# RoboSlider.net
KiCad netlist of a schematic drawn in EAGLE
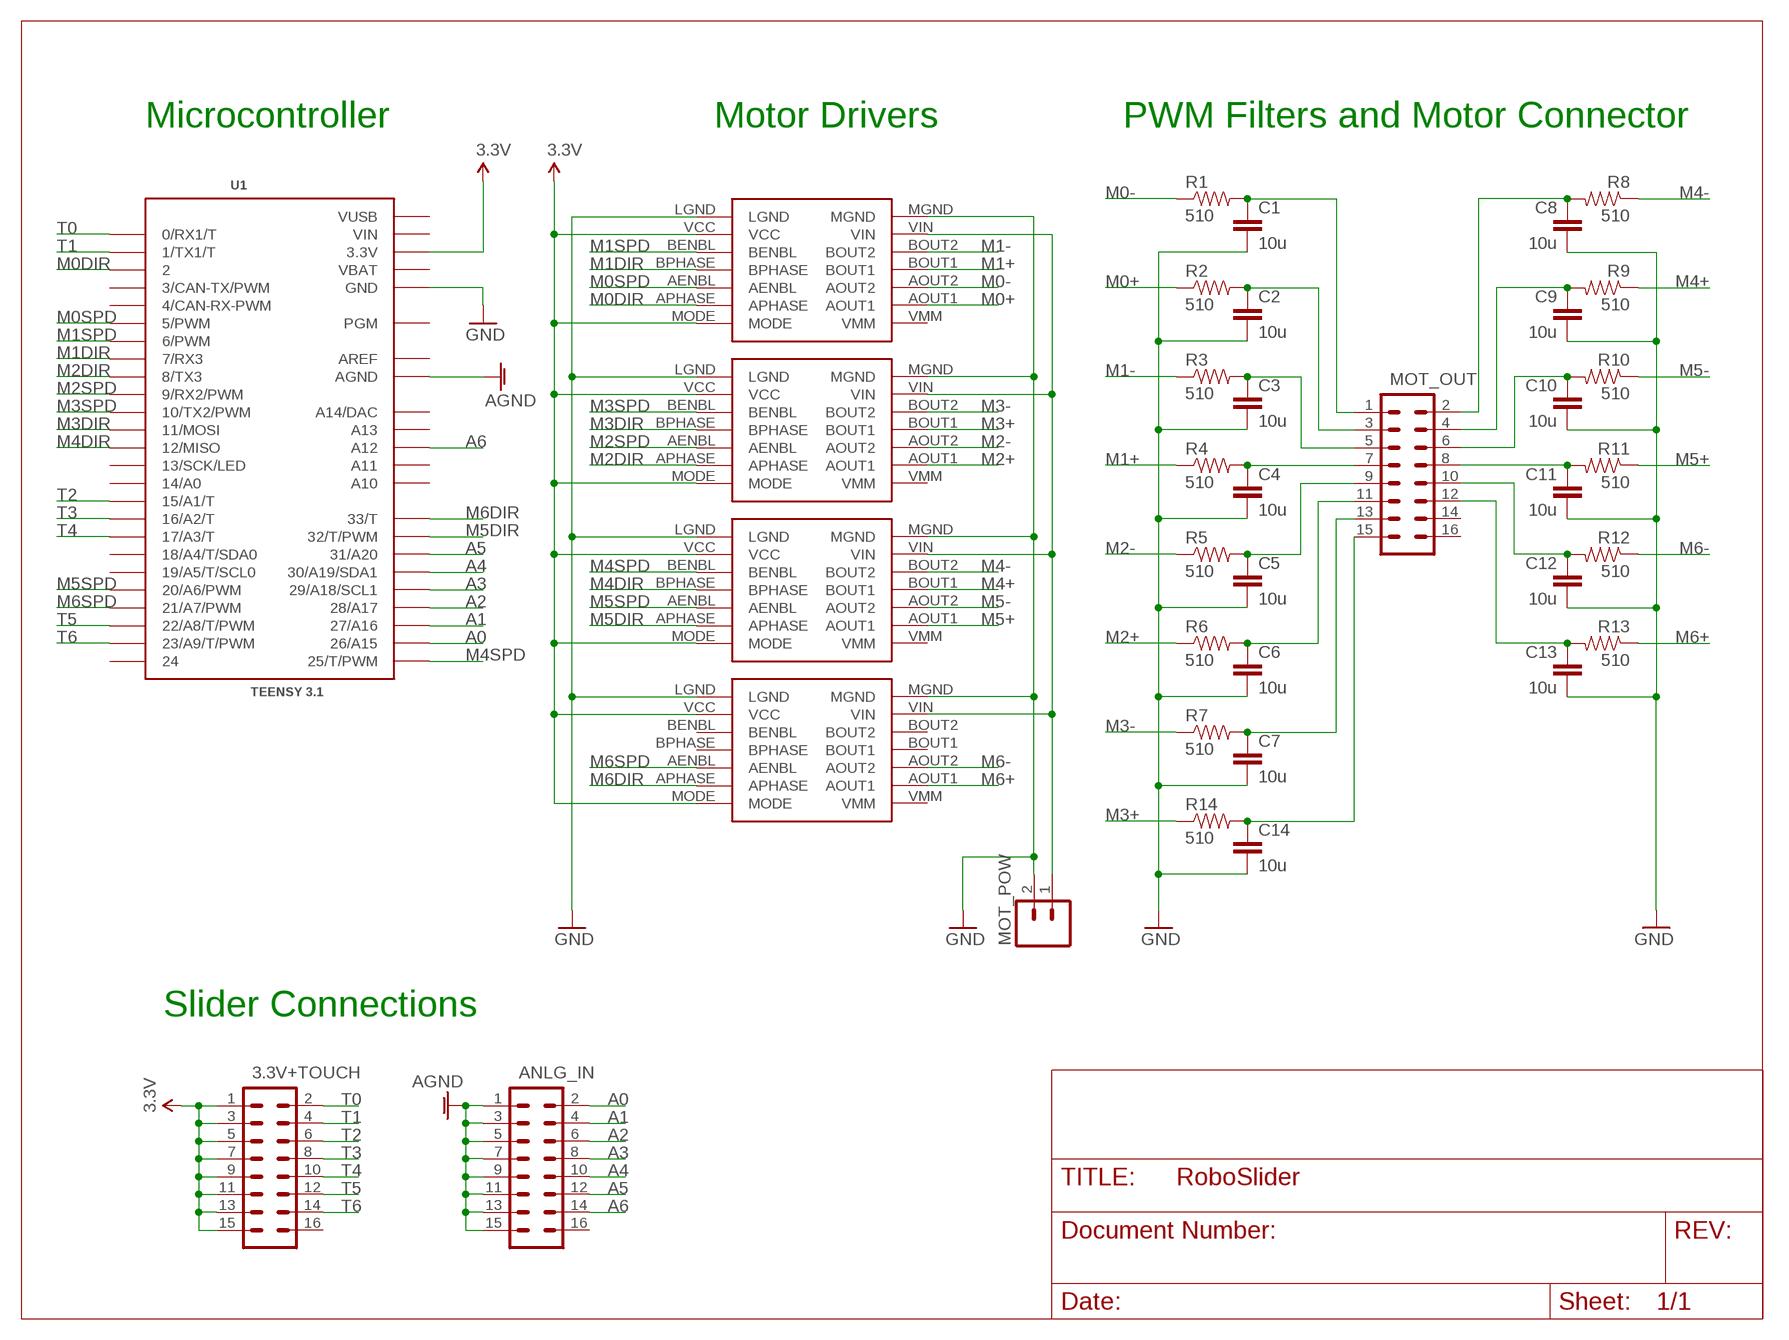
[diagram p0: schematic, sheet 1]

(export (version "E")
  (design (tool "Eeschema 10.0.6"))
  (components
    (comp (ref "3.3V+TOUCH")
      (value "M08X2")
      (footprint "eagle-import:2X8")
      (libsource (lib "eagle-import") (part "M08X2"))
    )
    (comp (ref "ANLG_IN")
      (value "M08X2")
      (footprint "eagle-import:2X8")
      (libsource (lib "eagle-import") (part "M08X2"))
    )
    (comp (ref "C1")
      (value "10u")
      (footprint "eagle-import:CAP-PTH-SMALL")
      (libsource (lib "eagle-import") (part "CAPPTH"))
    )
    (comp (ref "C2")
      (value "10u")
      (footprint "eagle-import:CAP-PTH-SMALL")
      (libsource (lib "eagle-import") (part "CAPPTH"))
    )
    (comp (ref "C3")
      (value "10u")
      (footprint "eagle-import:CAP-PTH-SMALL")
      (libsource (lib "eagle-import") (part "CAPPTH"))
    )
    (comp (ref "C4")
      (value "10u")
      (footprint "eagle-import:CAP-PTH-SMALL")
      (libsource (lib "eagle-import") (part "CAPPTH"))
    )
    (comp (ref "C5")
      (value "10u")
      (footprint "eagle-import:CAP-PTH-SMALL")
      (libsource (lib "eagle-import") (part "CAPPTH"))
    )
    (comp (ref "C6")
      (value "10u")
      (footprint "eagle-import:CAP-PTH-SMALL")
      (libsource (lib "eagle-import") (part "CAPPTH"))
    )
    (comp (ref "C7")
      (value "10u")
      (footprint "eagle-import:CAP-PTH-SMALL")
      (libsource (lib "eagle-import") (part "CAPPTH"))
    )
    (comp (ref "C8")
      (value "10u")
      (footprint "eagle-import:CAP-PTH-SMALL")
      (libsource (lib "eagle-import") (part "CAPPTH"))
    )
    (comp (ref "C9")
      (value "10u")
      (footprint "eagle-import:CAP-PTH-SMALL")
      (libsource (lib "eagle-import") (part "CAPPTH"))
    )
    (comp (ref "C10")
      (value "10u")
      (footprint "eagle-import:CAP-PTH-SMALL")
      (libsource (lib "eagle-import") (part "CAPPTH"))
    )
    (comp (ref "C11")
      (value "10u")
      (footprint "eagle-import:CAP-PTH-SMALL")
      (libsource (lib "eagle-import") (part "CAPPTH"))
    )
    (comp (ref "C12")
      (value "10u")
      (footprint "eagle-import:CAP-PTH-SMALL")
      (libsource (lib "eagle-import") (part "CAPPTH"))
    )
    (comp (ref "C13")
      (value "10u")
      (footprint "eagle-import:CAP-PTH-SMALL")
      (libsource (lib "eagle-import") (part "CAPPTH"))
    )
    (comp (ref "C14")
      (value "10u")
      (footprint "eagle-import:CAP-PTH-SMALL")
      (libsource (lib "eagle-import") (part "CAPPTH"))
    )
    (comp (ref "MOT_OUT")
      (value "M08X2")
      (footprint "eagle-import:2X8")
      (libsource (lib "eagle-import") (part "M08X2"))
    )
    (comp (ref "MOT_POW")
      (value "M02PTH")
      (footprint "eagle-import:1X02")
      (libsource (lib "eagle-import") (part "M02PTH"))
    )
    (comp (ref "R1")
      (value "510")
      (footprint "eagle-import:AXIAL-0.3")
      (libsource (lib "eagle-import") (part "RESISTORAXIAL-0.3"))
    )
    (comp (ref "R2")
      (value "510")
      (footprint "eagle-import:AXIAL-0.3")
      (libsource (lib "eagle-import") (part "RESISTORAXIAL-0.3"))
    )
    (comp (ref "R3")
      (value "510")
      (footprint "eagle-import:AXIAL-0.3")
      (libsource (lib "eagle-import") (part "RESISTORAXIAL-0.3"))
    )
    (comp (ref "R4")
      (value "510")
      (footprint "eagle-import:AXIAL-0.3")
      (libsource (lib "eagle-import") (part "RESISTORAXIAL-0.3"))
    )
    (comp (ref "R5")
      (value "510")
      (footprint "eagle-import:AXIAL-0.3")
      (libsource (lib "eagle-import") (part "RESISTORAXIAL-0.3"))
    )
    (comp (ref "R6")
      (value "510")
      (footprint "eagle-import:AXIAL-0.3")
      (libsource (lib "eagle-import") (part "RESISTORAXIAL-0.3"))
    )
    (comp (ref "R7")
      (value "510")
      (footprint "eagle-import:AXIAL-0.3")
      (libsource (lib "eagle-import") (part "RESISTORAXIAL-0.3"))
    )
    (comp (ref "R8")
      (value "510")
      (footprint "eagle-import:AXIAL-0.3")
      (libsource (lib "eagle-import") (part "RESISTORAXIAL-0.3"))
    )
    (comp (ref "R9")
      (value "510")
      (footprint "eagle-import:AXIAL-0.3")
      (libsource (lib "eagle-import") (part "RESISTORAXIAL-0.3"))
    )
    (comp (ref "R10")
      (value "510")
      (footprint "eagle-import:AXIAL-0.3")
      (libsource (lib "eagle-import") (part "RESISTORAXIAL-0.3"))
    )
    (comp (ref "R11")
      (value "510")
      (footprint "eagle-import:AXIAL-0.3")
      (libsource (lib "eagle-import") (part "RESISTORAXIAL-0.3"))
    )
    (comp (ref "R12")
      (value "510")
      (footprint "eagle-import:AXIAL-0.3")
      (libsource (lib "eagle-import") (part "RESISTORAXIAL-0.3"))
    )
    (comp (ref "R13")
      (value "510")
      (footprint "eagle-import:AXIAL-0.3")
      (libsource (lib "eagle-import") (part "RESISTORAXIAL-0.3"))
    )
    (comp (ref "R14")
      (value "510")
      (footprint "eagle-import:AXIAL-0.3")
      (libsource (lib "eagle-import") (part "RESISTORAXIAL-0.3"))
    )
    (comp (ref "U$1")
      (value "POLOLU_MOTOR_DRV8835THROUGHHOLE")
      (footprint "eagle-import:POLOLU_MOTOR_DRV_DRV8835")
      (libsource (lib "eagle-import") (part "POLOLU_MOTOR_DRV8835THROUGHHOLE"))
    )
    (comp (ref "U$2")
      (value "POLOLU_MOTOR_DRV8835THROUGHHOLE")
      (footprint "eagle-import:POLOLU_MOTOR_DRV_DRV8835")
      (libsource (lib "eagle-import") (part "POLOLU_MOTOR_DRV8835THROUGHHOLE"))
    )
    (comp (ref "U$3")
      (value "POLOLU_MOTOR_DRV8835THROUGHHOLE")
      (footprint "eagle-import:POLOLU_MOTOR_DRV_DRV8835")
      (libsource (lib "eagle-import") (part "POLOLU_MOTOR_DRV8835THROUGHHOLE"))
    )
    (comp (ref "U$4")
      (value "POLOLU_MOTOR_DRV8835THROUGHHOLE")
      (footprint "eagle-import:POLOLU_MOTOR_DRV_DRV8835")
      (libsource (lib "eagle-import") (part "POLOLU_MOTOR_DRV8835THROUGHHOLE"))
    )
    (comp (ref "U1")
      (value "TEENSY 3.1")
      (footprint "eagle-import:TEENSY_3.1_ALLPINS")
      (libsource (lib "eagle-import") (part "TEENSY_3.1_ALL_PINS_AND_PADS"))
    )
  )
  (nets
    (net (code "1") (name "/A0") (class "Default")
      (node (ref "ANLG_IN") (pin "2") (pinfunction "2_2") (pintype "passive"))
      (node (ref "U1") (pin "26") (pinfunction "26/A15_26") (pintype "bidirectional"))
    )
    (net (code "2") (name "/A1") (class "Default")
      (node (ref "ANLG_IN") (pin "4") (pinfunction "4_4") (pintype "passive"))
      (node (ref "U1") (pin "27") (pinfunction "27/A16_27") (pintype "bidirectional"))
    )
    (net (code "3") (name "/A2") (class "Default")
      (node (ref "ANLG_IN") (pin "6") (pinfunction "6_6") (pintype "passive"))
      (node (ref "U1") (pin "28") (pinfunction "28/A17_28") (pintype "bidirectional"))
    )
    (net (code "4") (name "/A3") (class "Default")
      (node (ref "ANLG_IN") (pin "8") (pinfunction "8_8") (pintype "passive"))
      (node (ref "U1") (pin "29") (pinfunction "29/A18/SCL1_29") (pintype "bidirectional"))
    )
    (net (code "5") (name "/A4") (class "Default")
      (node (ref "ANLG_IN") (pin "10") (pinfunction "10_10") (pintype "passive"))
      (node (ref "U1") (pin "30") (pinfunction "30/A19/SDA1_30") (pintype "bidirectional"))
    )
    (net (code "6") (name "/A5") (class "Default")
      (node (ref "ANLG_IN") (pin "12") (pinfunction "12_12") (pintype "passive"))
      (node (ref "U1") (pin "31") (pinfunction "31/A20_31") (pintype "bidirectional"))
    )
    (net (code "7") (name "/A6") (class "Default")
      (node (ref "ANLG_IN") (pin "14") (pinfunction "14_14") (pintype "passive"))
      (node (ref "U1") (pin "A12") (pinfunction "A12_A12") (pintype "bidirectional"))
    )
    (net (code "8") (name "/AREF") (class "Default")
      (node (ref "U1") (pin "AREF") (pinfunction "AREF_AREF") (pintype "power_in"))
    )
    (net (code "9") (name "/M0+") (class "Default")
      (node (ref "R2") (pin "P$1") (pinfunction "1_P$1") (pintype "passive"))
      (node (ref "U$1") (pin "AOUT1") (pinfunction "AOUT1_AOUT1") (pintype "bidirectional"))
    )
    (net (code "10") (name "/M0-") (class "Default")
      (node (ref "R1") (pin "P$1") (pinfunction "1_P$1") (pintype "passive"))
      (node (ref "U$1") (pin "AOUT2") (pinfunction "AOUT2_AOUT2") (pintype "bidirectional"))
    )
    (net (code "11") (name "/M0DIR") (class "Default")
      (node (ref "U$1") (pin "APHASE") (pinfunction "APHASE_APHASE") (pintype "bidirectional"))
      (node (ref "U1") (pin "2") (pinfunction "2_2") (pintype "bidirectional"))
    )
    (net (code "12") (name "/M0SPD") (class "Default")
      (node (ref "U$1") (pin "AENBL") (pinfunction "AENBL_AENBL") (pintype "bidirectional"))
      (node (ref "U1") (pin "5") (pinfunction "5/PWM_5") (pintype "bidirectional"))
    )
    (net (code "13") (name "/M1+") (class "Default")
      (node (ref "R4") (pin "P$1") (pinfunction "1_P$1") (pintype "passive"))
      (node (ref "U$1") (pin "BOUT1") (pinfunction "BOUT1_BOUT1") (pintype "bidirectional"))
    )
    (net (code "14") (name "/M1-") (class "Default")
      (node (ref "R3") (pin "P$1") (pinfunction "1_P$1") (pintype "passive"))
      (node (ref "U$1") (pin "BOUT2") (pinfunction "BOUT2_BOUT2") (pintype "bidirectional"))
    )
    (net (code "15") (name "/M1DIR") (class "Default")
      (node (ref "U$1") (pin "BPHASE") (pinfunction "BPHASE_BPHASE") (pintype "bidirectional"))
      (node (ref "U1") (pin "7") (pinfunction "7/RX3_7") (pintype "bidirectional"))
    )
    (net (code "16") (name "/M1SPD") (class "Default")
      (node (ref "U$1") (pin "BENBL") (pinfunction "BENBL_BENBL") (pintype "bidirectional"))
      (node (ref "U1") (pin "6") (pinfunction "6/PWM_6") (pintype "bidirectional"))
    )
    (net (code "17") (name "/M2+") (class "Default")
      (node (ref "R6") (pin "P$1") (pinfunction "1_P$1") (pintype "passive"))
      (node (ref "U$2") (pin "AOUT1") (pinfunction "AOUT1_AOUT1") (pintype "bidirectional"))
    )
    (net (code "18") (name "/M2-") (class "Default")
      (node (ref "R5") (pin "P$1") (pinfunction "1_P$1") (pintype "passive"))
      (node (ref "U$2") (pin "AOUT2") (pinfunction "AOUT2_AOUT2") (pintype "bidirectional"))
    )
    (net (code "19") (name "/M2DIR") (class "Default")
      (node (ref "U$2") (pin "APHASE") (pinfunction "APHASE_APHASE") (pintype "bidirectional"))
      (node (ref "U1") (pin "8") (pinfunction "8/TX3_8") (pintype "bidirectional"))
    )
    (net (code "20") (name "/M2SPD") (class "Default")
      (node (ref "U$2") (pin "AENBL") (pinfunction "AENBL_AENBL") (pintype "bidirectional"))
      (node (ref "U1") (pin "9") (pinfunction "9/RX2/PWM_9") (pintype "bidirectional"))
    )
    (net (code "21") (name "/M3+") (class "Default")
      (node (ref "R14") (pin "P$1") (pinfunction "1_P$1") (pintype "passive"))
      (node (ref "U$2") (pin "BOUT1") (pinfunction "BOUT1_BOUT1") (pintype "bidirectional"))
    )
    (net (code "22") (name "/M3-") (class "Default")
      (node (ref "R7") (pin "P$1") (pinfunction "1_P$1") (pintype "passive"))
      (node (ref "U$2") (pin "BOUT2") (pinfunction "BOUT2_BOUT2") (pintype "bidirectional"))
    )
    (net (code "23") (name "/M3DIR") (class "Default")
      (node (ref "U$2") (pin "BPHASE") (pinfunction "BPHASE_BPHASE") (pintype "bidirectional"))
      (node (ref "U1") (pin "11") (pinfunction "11/MOSI_11") (pintype "bidirectional"))
    )
    (net (code "24") (name "/M3SPD") (class "Default")
      (node (ref "U$2") (pin "BENBL") (pinfunction "BENBL_BENBL") (pintype "bidirectional"))
      (node (ref "U1") (pin "10") (pinfunction "10/TX2/PWM_10") (pintype "bidirectional"))
    )
    (net (code "25") (name "/M4+") (class "Default")
      (node (ref "R9") (pin "P$1") (pinfunction "1_P$1") (pintype "passive"))
      (node (ref "U$3") (pin "BOUT1") (pinfunction "BOUT1_BOUT1") (pintype "bidirectional"))
    )
    (net (code "26") (name "/M4-") (class "Default")
      (node (ref "R8") (pin "P$1") (pinfunction "1_P$1") (pintype "passive"))
      (node (ref "U$3") (pin "BOUT2") (pinfunction "BOUT2_BOUT2") (pintype "bidirectional"))
    )
    (net (code "27") (name "/M4DIR") (class "Default")
      (node (ref "U$3") (pin "BPHASE") (pinfunction "BPHASE_BPHASE") (pintype "bidirectional"))
      (node (ref "U1") (pin "12") (pinfunction "12/MISO_12") (pintype "bidirectional"))
    )
    (net (code "28") (name "/M4SPD") (class "Default")
      (node (ref "U$3") (pin "BENBL") (pinfunction "BENBL_BENBL") (pintype "bidirectional"))
      (node (ref "U1") (pin "25") (pinfunction "25/T/PWM_25") (pintype "bidirectional"))
    )
    (net (code "29") (name "/M5+") (class "Default")
      (node (ref "R11") (pin "P$1") (pinfunction "1_P$1") (pintype "passive"))
      (node (ref "U$3") (pin "AOUT1") (pinfunction "AOUT1_AOUT1") (pintype "bidirectional"))
    )
    (net (code "30") (name "/M5-") (class "Default")
      (node (ref "R10") (pin "P$1") (pinfunction "1_P$1") (pintype "passive"))
      (node (ref "U$3") (pin "AOUT2") (pinfunction "AOUT2_AOUT2") (pintype "bidirectional"))
    )
    (net (code "31") (name "/M5DIR") (class "Default")
      (node (ref "U$3") (pin "APHASE") (pinfunction "APHASE_APHASE") (pintype "bidirectional"))
      (node (ref "U1") (pin "32") (pinfunction "32/T/PWM_32") (pintype "bidirectional"))
    )
    (net (code "32") (name "/M5SPD") (class "Default")
      (node (ref "U$3") (pin "AENBL") (pinfunction "AENBL_AENBL") (pintype "bidirectional"))
      (node (ref "U1") (pin "20/A6") (pinfunction "20/A6/PWM_20/A6") (pintype "bidirectional"))
    )
    (net (code "33") (name "/M6+") (class "Default")
      (node (ref "R13") (pin "P$1") (pinfunction "1_P$1") (pintype "passive"))
      (node (ref "U$4") (pin "AOUT1") (pinfunction "AOUT1_AOUT1") (pintype "bidirectional"))
    )
    (net (code "34") (name "/M6-") (class "Default")
      (node (ref "R12") (pin "P$1") (pinfunction "1_P$1") (pintype "passive"))
      (node (ref "U$4") (pin "AOUT2") (pinfunction "AOUT2_AOUT2") (pintype "bidirectional"))
    )
    (net (code "35") (name "/M6DIR") (class "Default")
      (node (ref "U$4") (pin "APHASE") (pinfunction "APHASE_APHASE") (pintype "bidirectional"))
      (node (ref "U1") (pin "33") (pinfunction "33/T_33") (pintype "bidirectional"))
    )
    (net (code "36") (name "/M6SPD") (class "Default")
      (node (ref "U$4") (pin "AENBL") (pinfunction "AENBL_AENBL") (pintype "bidirectional"))
      (node (ref "U1") (pin "21/A7") (pinfunction "21/A7/PWM_21/A7") (pintype "bidirectional"))
    )
    (net (code "37") (name "/T0") (class "Default")
      (node (ref "3.3V+TOUCH") (pin "2") (pinfunction "2_2") (pintype "passive"))
      (node (ref "U1") (pin "0") (pinfunction "0/RX1/T_0") (pintype "bidirectional"))
    )
    (net (code "38") (name "/T1") (class "Default")
      (node (ref "3.3V+TOUCH") (pin "4") (pinfunction "4_4") (pintype "passive"))
      (node (ref "U1") (pin "1") (pinfunction "1/TX1/T_1") (pintype "bidirectional"))
    )
    (net (code "39") (name "/T2") (class "Default")
      (node (ref "3.3V+TOUCH") (pin "6") (pinfunction "6_6") (pintype "passive"))
      (node (ref "U1") (pin "15/A1") (pinfunction "15/A1/T_15/A1") (pintype "bidirectional"))
    )
    (net (code "40") (name "/T3") (class "Default")
      (node (ref "3.3V+TOUCH") (pin "8") (pinfunction "8_8") (pintype "passive"))
      (node (ref "U1") (pin "16/A2") (pinfunction "16/A2/T_16/A2") (pintype "bidirectional"))
    )
    (net (code "41") (name "/T4") (class "Default")
      (node (ref "3.3V+TOUCH") (pin "10") (pinfunction "10_10") (pintype "passive"))
      (node (ref "U1") (pin "17/A3") (pinfunction "17/A3/T_17/A3") (pintype "bidirectional"))
    )
    (net (code "42") (name "/T5") (class "Default")
      (node (ref "3.3V+TOUCH") (pin "12") (pinfunction "12_12") (pintype "passive"))
      (node (ref "U1") (pin "22/A8") (pinfunction "22/A8/T/PWM_22/A8") (pintype "bidirectional"))
    )
    (net (code "43") (name "/T6") (class "Default")
      (node (ref "3.3V+TOUCH") (pin "14") (pinfunction "14_14") (pintype "passive"))
      (node (ref "U1") (pin "23/A9") (pinfunction "23/A9/T/PWM_23/A9") (pintype "bidirectional"))
    )
    (net (code "44") (name "/VBAT") (class "Default")
      (node (ref "U1") (pin "VBAT") (pinfunction "VBAT_VBAT") (pintype "power_in"))
    )
    (net (code "45") (name "/VIN") (class "Default")
      (node (ref "U1") (pin "VIN") (pinfunction "VIN_VIN") (pintype "power_in"))
    )
    (net (code "46") (name "/VUSB") (class "Default")
      (node (ref "U1") (pin "VUSB") (pinfunction "VUSB_VUSB") (pintype "power_in"))
    )
    (net (code "47") (name "3.3V") (class "Default")
      (node (ref "3.3V+TOUCH") (pin "1") (pinfunction "1_1") (pintype "passive"))
      (node (ref "3.3V+TOUCH") (pin "11") (pinfunction "11_11") (pintype "passive"))
      (node (ref "3.3V+TOUCH") (pin "13") (pinfunction "13_13") (pintype "passive"))
      (node (ref "3.3V+TOUCH") (pin "15") (pinfunction "15_15") (pintype "passive"))
      (node (ref "3.3V+TOUCH") (pin "3") (pinfunction "3_3") (pintype "passive"))
      (node (ref "3.3V+TOUCH") (pin "5") (pinfunction "5_5") (pintype "passive"))
      (node (ref "3.3V+TOUCH") (pin "7") (pinfunction "7_7") (pintype "passive"))
      (node (ref "3.3V+TOUCH") (pin "9") (pinfunction "9_9") (pintype "passive"))
      (node (ref "U$1") (pin "MODE") (pinfunction "MODE_MODE") (pintype "bidirectional"))
      (node (ref "U$1") (pin "VCC") (pinfunction "VCC_VCC") (pintype "bidirectional"))
      (node (ref "U$2") (pin "MODE") (pinfunction "MODE_MODE") (pintype "bidirectional"))
      (node (ref "U$2") (pin "VCC") (pinfunction "VCC_VCC") (pintype "bidirectional"))
      (node (ref "U$3") (pin "MODE") (pinfunction "MODE_MODE") (pintype "bidirectional"))
      (node (ref "U$3") (pin "VCC") (pinfunction "VCC_VCC") (pintype "bidirectional"))
      (node (ref "U$4") (pin "MODE") (pinfunction "MODE_MODE") (pintype "bidirectional"))
      (node (ref "U$4") (pin "VCC") (pinfunction "VCC_VCC") (pintype "bidirectional"))
      (node (ref "U1") (pin "3.3V") (pinfunction "3.3V_3.3V") (pintype "power_in"))
      (node (ref "U1") (pin "3.3V1") (pinfunction "3.3V_3.3V1") (pintype "power_in"))
      (node (ref "U1") (pin "3.3V2") (pinfunction "3.3V_3.3V2") (pintype "power_in"))
    )
    (net (code "48") (name "AGND") (class "Default")
      (node (ref "ANLG_IN") (pin "1") (pinfunction "1_1") (pintype "passive"))
      (node (ref "ANLG_IN") (pin "11") (pinfunction "11_11") (pintype "passive"))
      (node (ref "ANLG_IN") (pin "13") (pinfunction "13_13") (pintype "passive"))
      (node (ref "ANLG_IN") (pin "15") (pinfunction "15_15") (pintype "passive"))
      (node (ref "ANLG_IN") (pin "3") (pinfunction "3_3") (pintype "passive"))
      (node (ref "ANLG_IN") (pin "5") (pinfunction "5_5") (pintype "passive"))
      (node (ref "ANLG_IN") (pin "7") (pinfunction "7_7") (pintype "passive"))
      (node (ref "ANLG_IN") (pin "9") (pinfunction "9_9") (pintype "passive"))
      (node (ref "U1") (pin "AGND") (pinfunction "AGND_AGND") (pintype "power_in"))
    )
    (net (code "49") (name "GND") (class "Default")
      (node (ref "C1") (pin "2") (pinfunction "2_2") (pintype "passive"))
      (node (ref "C10") (pin "2") (pinfunction "2_2") (pintype "passive"))
      (node (ref "C11") (pin "2") (pinfunction "2_2") (pintype "passive"))
      (node (ref "C12") (pin "2") (pinfunction "2_2") (pintype "passive"))
      (node (ref "C13") (pin "2") (pinfunction "2_2") (pintype "passive"))
      (node (ref "C14") (pin "2") (pinfunction "2_2") (pintype "passive"))
      (node (ref "C2") (pin "2") (pinfunction "2_2") (pintype "passive"))
      (node (ref "C3") (pin "2") (pinfunction "2_2") (pintype "passive"))
      (node (ref "C4") (pin "2") (pinfunction "2_2") (pintype "passive"))
      (node (ref "C5") (pin "2") (pinfunction "2_2") (pintype "passive"))
      (node (ref "C6") (pin "2") (pinfunction "2_2") (pintype "passive"))
      (node (ref "C7") (pin "2") (pinfunction "2_2") (pintype "passive"))
      (node (ref "C8") (pin "2") (pinfunction "2_2") (pintype "passive"))
      (node (ref "C9") (pin "2") (pinfunction "2_2") (pintype "passive"))
      (node (ref "MOT_POW") (pin "2") (pinfunction "2_2") (pintype "passive"))
      (node (ref "U$1") (pin "LGND") (pinfunction "LGND_LGND") (pintype "bidirectional"))
      (node (ref "U$1") (pin "MGND") (pinfunction "MGND_MGND") (pintype "bidirectional"))
      (node (ref "U$2") (pin "LGND") (pinfunction "LGND_LGND") (pintype "bidirectional"))
      (node (ref "U$2") (pin "MGND") (pinfunction "MGND_MGND") (pintype "bidirectional"))
      (node (ref "U$3") (pin "LGND") (pinfunction "LGND_LGND") (pintype "bidirectional"))
      (node (ref "U$3") (pin "MGND") (pinfunction "MGND_MGND") (pintype "bidirectional"))
      (node (ref "U$4") (pin "LGND") (pinfunction "LGND_LGND") (pintype "bidirectional"))
      (node (ref "U$4") (pin "MGND") (pinfunction "MGND_MGND") (pintype "bidirectional"))
      (node (ref "U1") (pin "GND") (pinfunction "GND_GND") (pintype "power_in"))
      (node (ref "U1") (pin "GND1") (pinfunction "GND_GND1") (pintype "power_in"))
      (node (ref "U1") (pin "GND2") (pinfunction "GND_GND2") (pintype "power_in"))
    )
    (net (code "50") (name "Net-(MOT_POW-Pad1)") (class "Default")
      (node (ref "MOT_POW") (pin "1") (pinfunction "1_1") (pintype "passive"))
      (node (ref "U$1") (pin "VIN") (pinfunction "VIN_VIN") (pintype "bidirectional"))
      (node (ref "U$2") (pin "VIN") (pinfunction "VIN_VIN") (pintype "bidirectional"))
      (node (ref "U$3") (pin "VIN") (pinfunction "VIN_VIN") (pintype "bidirectional"))
      (node (ref "U$4") (pin "VIN") (pinfunction "VIN_VIN") (pintype "bidirectional"))
    )
    (net (code "51") (name "Net-(R1-2)") (class "Default")
      (node (ref "C1") (pin "1") (pinfunction "1_1") (pintype "passive"))
      (node (ref "MOT_OUT") (pin "1") (pinfunction "1_1") (pintype "passive"))
      (node (ref "R1") (pin "P$2") (pinfunction "2_P$2") (pintype "passive"))
    )
    (net (code "52") (name "Net-(R2-2)") (class "Default")
      (node (ref "C2") (pin "1") (pinfunction "1_1") (pintype "passive"))
      (node (ref "MOT_OUT") (pin "3") (pinfunction "3_3") (pintype "passive"))
      (node (ref "R2") (pin "P$2") (pinfunction "2_P$2") (pintype "passive"))
    )
    (net (code "53") (name "Net-(R3-2)") (class "Default")
      (node (ref "C3") (pin "1") (pinfunction "1_1") (pintype "passive"))
      (node (ref "MOT_OUT") (pin "5") (pinfunction "5_5") (pintype "passive"))
      (node (ref "R3") (pin "P$2") (pinfunction "2_P$2") (pintype "passive"))
    )
    (net (code "54") (name "Net-(R4-2)") (class "Default")
      (node (ref "C4") (pin "1") (pinfunction "1_1") (pintype "passive"))
      (node (ref "MOT_OUT") (pin "7") (pinfunction "7_7") (pintype "passive"))
      (node (ref "R4") (pin "P$2") (pinfunction "2_P$2") (pintype "passive"))
    )
    (net (code "55") (name "Net-(R5-2)") (class "Default")
      (node (ref "C5") (pin "1") (pinfunction "1_1") (pintype "passive"))
      (node (ref "MOT_OUT") (pin "9") (pinfunction "9_9") (pintype "passive"))
      (node (ref "R5") (pin "P$2") (pinfunction "2_P$2") (pintype "passive"))
    )
    (net (code "56") (name "Net-(R6-2)") (class "Default")
      (node (ref "C6") (pin "1") (pinfunction "1_1") (pintype "passive"))
      (node (ref "MOT_OUT") (pin "11") (pinfunction "11_11") (pintype "passive"))
      (node (ref "R6") (pin "P$2") (pinfunction "2_P$2") (pintype "passive"))
    )
    (net (code "57") (name "Net-(R7-2)") (class "Default")
      (node (ref "C7") (pin "1") (pinfunction "1_1") (pintype "passive"))
      (node (ref "MOT_OUT") (pin "13") (pinfunction "13_13") (pintype "passive"))
      (node (ref "R7") (pin "P$2") (pinfunction "2_P$2") (pintype "passive"))
    )
    (net (code "58") (name "Net-(R8-2)") (class "Default")
      (node (ref "C8") (pin "1") (pinfunction "1_1") (pintype "passive"))
      (node (ref "MOT_OUT") (pin "2") (pinfunction "2_2") (pintype "passive"))
      (node (ref "R8") (pin "P$2") (pinfunction "2_P$2") (pintype "passive"))
    )
    (net (code "59") (name "Net-(R9-2)") (class "Default")
      (node (ref "C9") (pin "1") (pinfunction "1_1") (pintype "passive"))
      (node (ref "MOT_OUT") (pin "4") (pinfunction "4_4") (pintype "passive"))
      (node (ref "R9") (pin "P$2") (pinfunction "2_P$2") (pintype "passive"))
    )
    (net (code "60") (name "Net-(R10-2)") (class "Default")
      (node (ref "C10") (pin "1") (pinfunction "1_1") (pintype "passive"))
      (node (ref "MOT_OUT") (pin "6") (pinfunction "6_6") (pintype "passive"))
      (node (ref "R10") (pin "P$2") (pinfunction "2_P$2") (pintype "passive"))
    )
    (net (code "61") (name "Net-(R11-2)") (class "Default")
      (node (ref "C11") (pin "1") (pinfunction "1_1") (pintype "passive"))
      (node (ref "MOT_OUT") (pin "8") (pinfunction "8_8") (pintype "passive"))
      (node (ref "R11") (pin "P$2") (pinfunction "2_P$2") (pintype "passive"))
    )
    (net (code "62") (name "Net-(R12-2)") (class "Default")
      (node (ref "C12") (pin "1") (pinfunction "1_1") (pintype "passive"))
      (node (ref "MOT_OUT") (pin "10") (pinfunction "10_10") (pintype "passive"))
      (node (ref "R12") (pin "P$2") (pinfunction "2_P$2") (pintype "passive"))
    )
    (net (code "63") (name "Net-(R13-2)") (class "Default")
      (node (ref "C13") (pin "1") (pinfunction "1_1") (pintype "passive"))
      (node (ref "MOT_OUT") (pin "12") (pinfunction "12_12") (pintype "passive"))
      (node (ref "R13") (pin "P$2") (pinfunction "2_P$2") (pintype "passive"))
    )
    (net (code "64") (name "Net-(R14-2)") (class "Default")
      (node (ref "C14") (pin "1") (pinfunction "1_1") (pintype "passive"))
      (node (ref "MOT_OUT") (pin "15") (pinfunction "15_15") (pintype "passive"))
      (node (ref "R14") (pin "P$2") (pinfunction "2_P$2") (pintype "passive"))
    )
    (net (code "65") (name "unconnected-(3.3V+TOUCH-Pad16)") (class "Default")
      (node (ref "3.3V+TOUCH") (pin "16") (pinfunction "16_16") (pintype "passive"))
    )
    (net (code "66") (name "unconnected-(ANLG_IN-Pad16)") (class "Default")
      (node (ref "ANLG_IN") (pin "16") (pinfunction "16_16") (pintype "passive"))
    )
    (net (code "67") (name "unconnected-(MOT_OUT-Pad14)") (class "Default")
      (node (ref "MOT_OUT") (pin "14") (pinfunction "14_14") (pintype "passive"))
    )
    (net (code "68") (name "unconnected-(MOT_OUT-Pad16)") (class "Default")
      (node (ref "MOT_OUT") (pin "16") (pinfunction "16_16") (pintype "passive"))
    )
    (net (code "69") (name "unconnected-(U$1-PadVMM)") (class "Default")
      (node (ref "U$1") (pin "VMM") (pinfunction "VMM_VMM") (pintype "bidirectional"))
    )
    (net (code "70") (name "unconnected-(U$2-PadVMM)") (class "Default")
      (node (ref "U$2") (pin "VMM") (pinfunction "VMM_VMM") (pintype "bidirectional"))
    )
    (net (code "71") (name "unconnected-(U$3-PadVMM)") (class "Default")
      (node (ref "U$3") (pin "VMM") (pinfunction "VMM_VMM") (pintype "bidirectional"))
    )
    (net (code "72") (name "unconnected-(U$4-PadBENBL)") (class "Default")
      (node (ref "U$4") (pin "BENBL") (pinfunction "BENBL_BENBL") (pintype "bidirectional"))
    )
    (net (code "73") (name "unconnected-(U$4-PadBOUT1)") (class "Default")
      (node (ref "U$4") (pin "BOUT1") (pinfunction "BOUT1_BOUT1") (pintype "bidirectional"))
    )
    (net (code "74") (name "unconnected-(U$4-PadBOUT2)") (class "Default")
      (node (ref "U$4") (pin "BOUT2") (pinfunction "BOUT2_BOUT2") (pintype "bidirectional"))
    )
    (net (code "75") (name "unconnected-(U$4-PadBPHASE)") (class "Default")
      (node (ref "U$4") (pin "BPHASE") (pinfunction "BPHASE_BPHASE") (pintype "bidirectional"))
    )
    (net (code "76") (name "unconnected-(U$4-PadVMM)") (class "Default")
      (node (ref "U$4") (pin "VMM") (pinfunction "VMM_VMM") (pintype "bidirectional"))
    )
    (net (code "77") (name "unconnected-(U1-3{slash}CAN-TX{slash}PWM-Pad3)") (class "Default")
      (node (ref "U1") (pin "3") (pinfunction "3/CAN-TX/PWM_3") (pintype "bidirectional"))
    )
    (net (code "78") (name "unconnected-(U1-4{slash}CAN-RX-PWM-Pad4)") (class "Default")
      (node (ref "U1") (pin "4") (pinfunction "4/CAN-RX-PWM_4") (pintype "bidirectional"))
    )
    (net (code "79") (name "unconnected-(U1-13{slash}SCK{slash}LED-Pad13)") (class "Default")
      (node (ref "U1") (pin "13") (pinfunction "13/SCK/LED_13") (pintype "bidirectional"))
    )
    (net (code "80") (name "unconnected-(U1-18{slash}A4{slash}T{slash}SDA0-Pad18{slash}A4)") (class "Default")
      (node (ref "U1") (pin "18/A4") (pinfunction "18/A4/T/SDA0_18/A4") (pintype "bidirectional"))
    )
    (net (code "81") (name "unconnected-(U1-19{slash}A5{slash}T{slash}SCL0-Pad19{slash}A5)") (class "Default")
      (node (ref "U1") (pin "19/A5") (pinfunction "19/A5/T/SCL0_19/A5") (pintype "bidirectional"))
    )
    (net (code "82") (name "unconnected-(U1-A14{slash}DAC-PadA14)") (class "Default")
      (node (ref "U1") (pin "A14") (pinfunction "A14/DAC_A14") (pintype "bidirectional"))
    )
    (net (code "83") (name "unconnected-(U1-Pad14{slash}A0)") (class "Default")
      (node (ref "U1") (pin "14/A0") (pinfunction "14/A0_14/A0") (pintype "bidirectional"))
    )
    (net (code "84") (name "unconnected-(U1-Pad24)") (class "Default")
      (node (ref "U1") (pin "24") (pinfunction "24_24") (pintype "bidirectional"))
    )
    (net (code "85") (name "unconnected-(U1-PadA10)") (class "Default")
      (node (ref "U1") (pin "A10") (pinfunction "A10_A10") (pintype "bidirectional"))
    )
    (net (code "86") (name "unconnected-(U1-PadA11)") (class "Default")
      (node (ref "U1") (pin "A11") (pinfunction "A11_A11") (pintype "bidirectional"))
    )
    (net (code "87") (name "unconnected-(U1-PadA13)") (class "Default")
      (node (ref "U1") (pin "A13") (pinfunction "A13_A13") (pintype "bidirectional"))
    )
    (net (code "88") (name "unconnected-(U1-PadPGM)") (class "Default")
      (node (ref "U1") (pin "PGM") (pinfunction "PGM_PGM") (pintype "bidirectional"))
    )
  )
)
